# button_LED.net
KiCad netlist of a schematic drawn in EAGLE
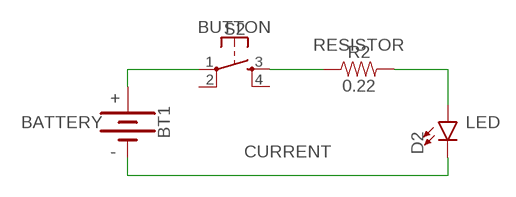
[diagram p0: schematic, sheet 1]

(export (version "E")
  (design (tool "Eeschema 10.0.6"))
  (components
    (comp (ref "BT1")
      (value "BATTERY-9V")
      (footprint "eagle-import:BATTCON_9V")
      (libsource (lib "eagle-import") (part "BATTERY-9V"))
    )
    (comp (ref "D2")
      (value "LED5MM")
      (footprint "eagle-import:LED_5MM")
      (libsource (lib "eagle-import") (part "LED5MM"))
    )
    (comp (ref "R2")
      (value "0.22")
      (footprint "eagle-import:0805")
      (libsource (lib "eagle-import") (part "0.22OHM-0805-1/4W-1%"))
    )
    (comp (ref "S2")
      (value "MOMENTARY-SWITCH-SPST-2-SMD-4.6X2.8MM")
      (footprint "eagle-import:TACTILE_SWITCH_SMD_4.6X2.8MM")
      (libsource (lib "eagle-import") (part "MOMENTARY-SWITCH-SPST-2-SMD-4.6X2.8MM"))
    )
  )
  (nets
    (net (code "1") (name "Net-(BT1-Pad+)") (class "Default")
      (node (ref "BT1") (pin "+") (pinfunction "+_+") (pintype "power_in"))
      (node (ref "S2") (pin "1") (pinfunction "1_1") (pintype "passive"))
    )
    (net (code "2") (name "Net-(D2-C)") (class "Default")
      (node (ref "BT1") (pin "-") (pinfunction "-_-") (pintype "power_in"))
      (node (ref "D2") (pin "K") (pinfunction "C_K") (pintype "passive"))
    )
    (net (code "3") (name "Net-(D2-PadA)") (class "Default")
      (node (ref "D2") (pin "A") (pinfunction "A_A") (pintype "passive"))
      (node (ref "R2") (pin "2") (pinfunction "2_2") (pintype "passive"))
    )
    (net (code "4") (name "Net-(R2-Pad1)") (class "Default")
      (node (ref "R2") (pin "1") (pinfunction "1_1") (pintype "passive"))
      (node (ref "S2") (pin "3") (pinfunction "3_3") (pintype "passive"))
    )
    (net (code "5") (name "unconnected-(S2-Pad2)") (class "Default")
      (node (ref "S2") (pin "2") (pinfunction "2_2") (pintype "passive"))
    )
    (net (code "6") (name "unconnected-(S2-Pad4)") (class "Default")
      (node (ref "S2") (pin "4") (pinfunction "4_4") (pintype "passive"))
    )
  )
)
